# SuperFin_Baseboard_pg8.net
KiCad netlist of a schematic drawn in Altium Designer
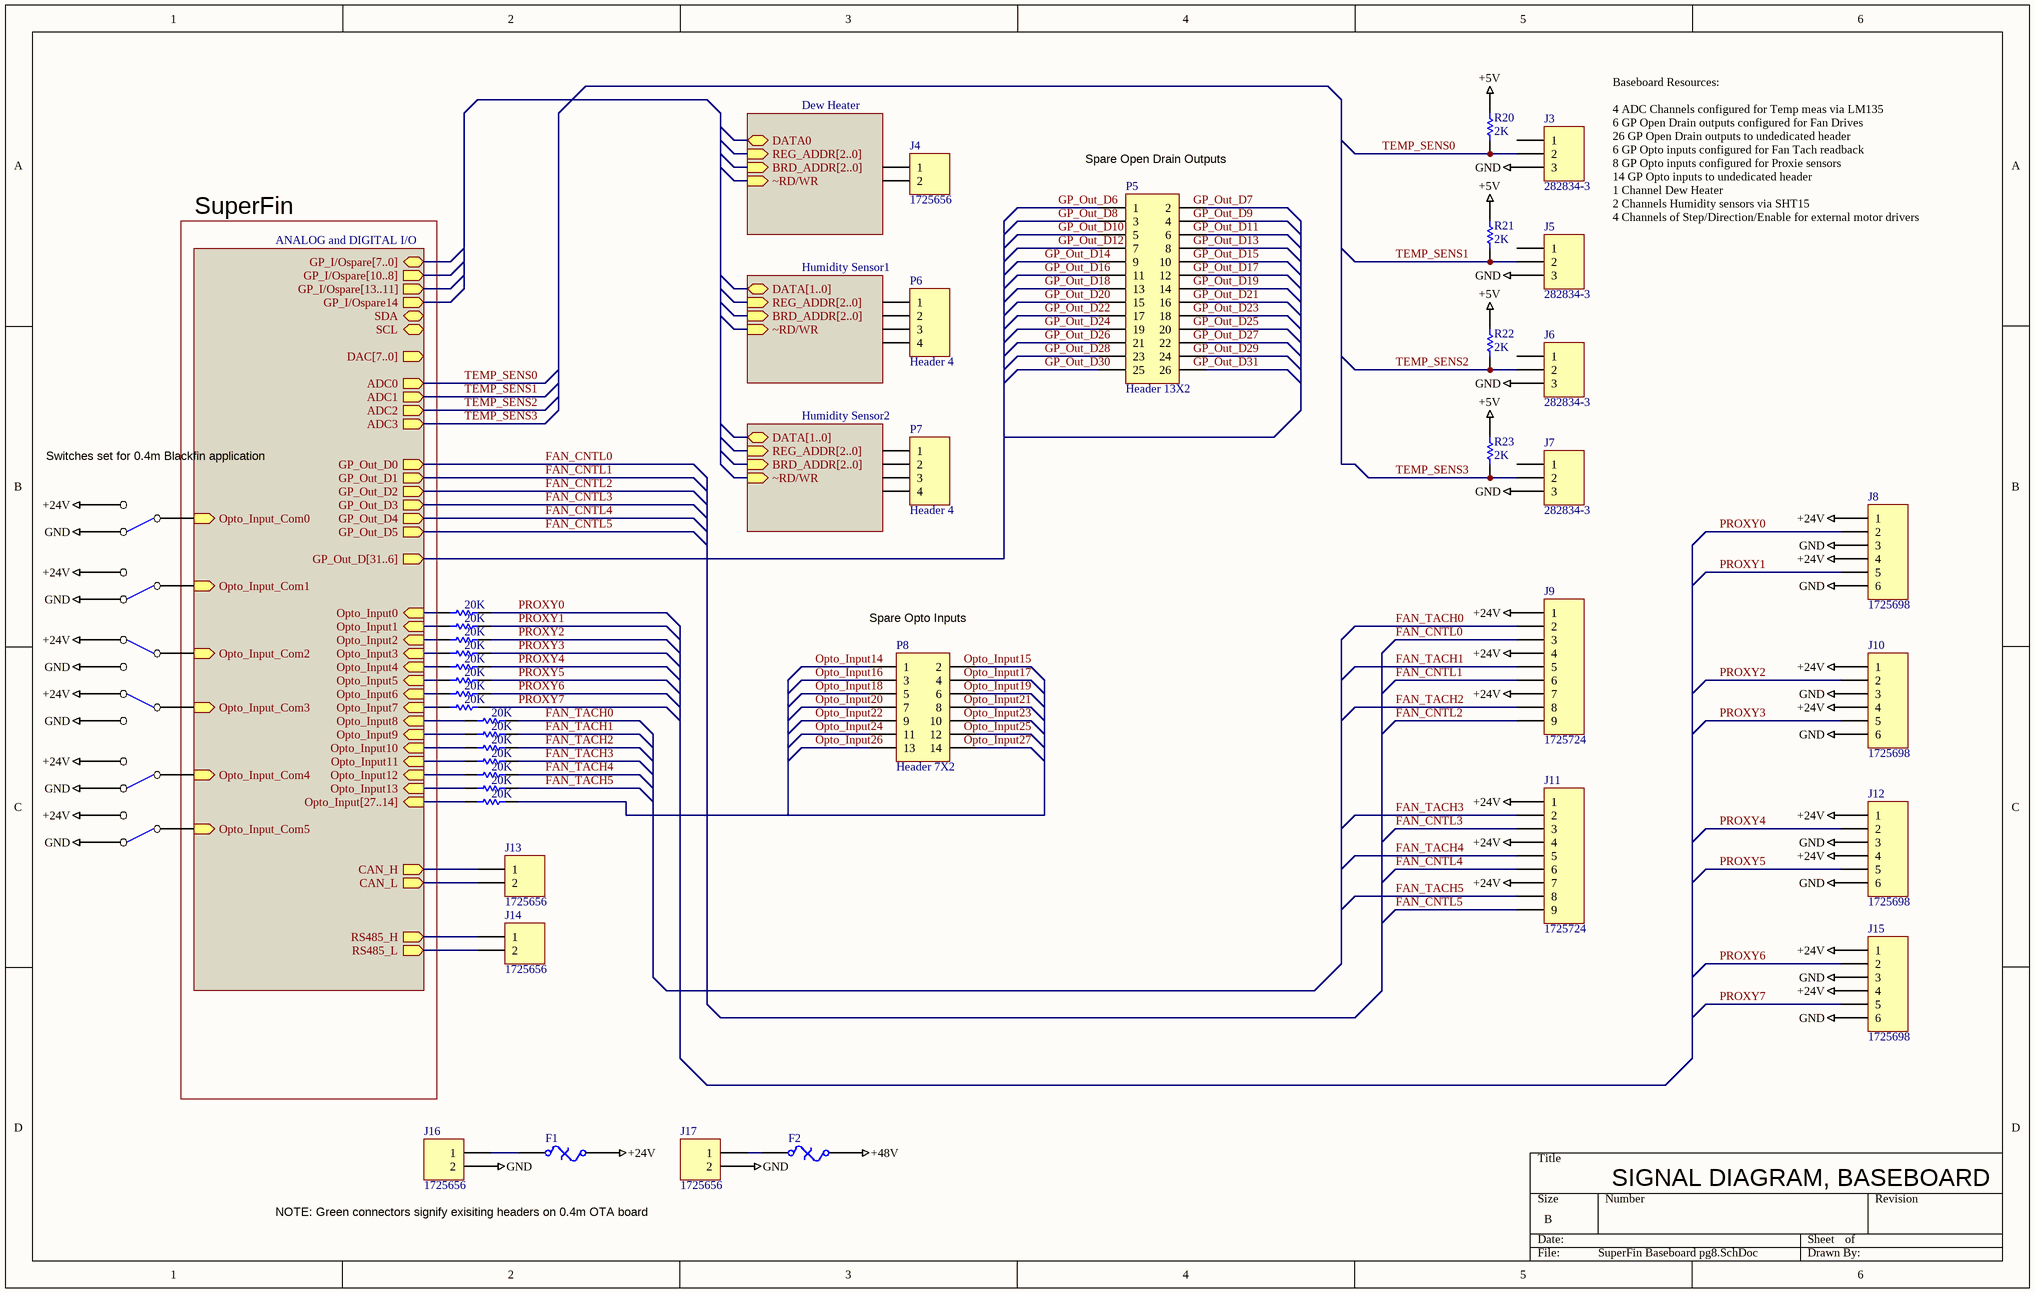
[diagram p0: SuperFin Baseboard pg8.SchDoc]

(export (version "E")
  (design (tool "Eeschema 10.0.6"))
  (components
    (comp (ref "*2") (value "SW_SPDT_DOUG") (libsource (lib "JON_1_Library") (part "SW_SPDT_DOUG")))
    (comp (ref "*3") (value "SW_SPDT_DOUG") (libsource (lib "JON_1_Library") (part "SW_SPDT_DOUG")))
    (comp (ref "*4") (value "SW_SPDT_DOUG") (libsource (lib "JON_1_Library") (part "SW_SPDT_DOUG")))
    (comp (ref "*5") (value "SW_SPDT_DOUG") (libsource (lib "JON_1_Library") (part "SW_SPDT_DOUG")))
    (comp (ref "*6") (value "SW_SPDT_DOUG") (libsource (lib "JON_1_Library") (part "SW_SPDT_DOUG")))
    (comp (ref "*7") (value "SW_SPDT_DOUG") (libsource (lib "JON_1_Library") (part "SW_SPDT_DOUG")))
    (comp (ref "F1")
      (value "Fuse Thermal")
      (footprint "PolySwitch Radial 0.2")
      (description "PolySwitch RUE Series")
      (libsource (lib "Richs Schematic Components") (part "Fuse Thermal"))
    )
    (comp (ref "F2")
      (value "Fuse Thermal")
      (footprint "PolySwitch Radial 0.2")
      (description "PolySwitch RUE Series")
      (libsource (lib "Richs Schematic Components") (part "Fuse Thermal"))
    )
    (comp (ref "J3")
      (value "282834-3")
      (footprint "Tyco Electronics 282834-3")
      (description "Header, 3-Pin")
      (fields (field (name "MANUFACTURER") "Tyco Electronics"))
      (libsource (lib "Miscellaneous Connectors") (part "Header 3"))
    )
    (comp (ref "J4")
      (value "1725656")
      (footprint "Phoenix_1725656")
      (description "Header, 2-Pin")
      (fields (field (name "MANUFACTURER") "Phoenix Contact"))
      (libsource (lib "Miscellaneous Connectors") (part "Header 2"))
    )
    (comp (ref "J5")
      (value "282834-3")
      (footprint "Tyco Electronics 282834-3")
      (description "Header, 3-Pin")
      (fields (field (name "MANUFACTURER") "Tyco Electronics"))
      (libsource (lib "Miscellaneous Connectors") (part "Header 3"))
    )
    (comp (ref "J6")
      (value "282834-3")
      (footprint "Tyco Electronics 282834-3")
      (description "Header, 3-Pin")
      (fields (field (name "MANUFACTURER") "Tyco Electronics"))
      (libsource (lib "Miscellaneous Connectors") (part "Header 3"))
    )
    (comp (ref "J7")
      (value "282834-3")
      (footprint "Tyco Electronics 282834-3")
      (description "Header, 3-Pin")
      (fields (field (name "MANUFACTURER") "Tyco Electronics"))
      (libsource (lib "Miscellaneous Connectors") (part "Header 3"))
    )
    (comp (ref "J8")
      (value "1725698")
      (footprint "1725698")
      (description "Header, 6-Pin")
      (fields (field (name "MANUFACTURER") "Phoenix Contact"))
      (libsource (lib "Miscellaneous Connectors") (part "Header 6"))
    )
    (comp (ref "J9")
      (value "1725724")
      (footprint "1725724")
      (description "Header, 9-Pin")
      (fields (field (name "MANUFACTURER") "Phoenix Contact"))
      (libsource (lib "Miscellaneous Connectors") (part "Header 9"))
    )
    (comp (ref "J10")
      (value "1725698")
      (footprint "1725698")
      (description "Header, 6-Pin")
      (fields (field (name "MANUFACTURER") "Phoenix Contact"))
      (libsource (lib "Miscellaneous Connectors") (part "Header 6"))
    )
    (comp (ref "J11")
      (value "1725724")
      (footprint "1725724")
      (description "Header, 9-Pin")
      (fields (field (name "MANUFACTURER") "Phoenix Contact"))
      (libsource (lib "Miscellaneous Connectors") (part "Header 9"))
    )
    (comp (ref "J12")
      (value "1725698")
      (footprint "1725698")
      (description "Header, 6-Pin")
      (fields (field (name "MANUFACTURER") "Phoenix Contact"))
      (libsource (lib "Miscellaneous Connectors") (part "Header 6"))
    )
    (comp (ref "J13")
      (value "1725656")
      (footprint "Phoenix_1725656")
      (description "Header, 2-Pin")
      (fields (field (name "MANUFACTURER") "Phoenix Contact"))
      (libsource (lib "Miscellaneous Connectors") (part "Header 2"))
    )
    (comp (ref "J14")
      (value "1725656")
      (footprint "Phoenix_1725656")
      (description "Header, 2-Pin")
      (fields (field (name "MANUFACTURER") "Phoenix Contact"))
      (libsource (lib "Miscellaneous Connectors") (part "Header 2"))
    )
    (comp (ref "J15")
      (value "1725698")
      (footprint "1725698")
      (description "Header, 6-Pin")
      (fields (field (name "MANUFACTURER") "Phoenix Contact"))
      (libsource (lib "Miscellaneous Connectors") (part "Header 6"))
    )
    (comp (ref "J16")
      (value "1725656")
      (footprint "Phoenix_1725656")
      (description "Header, 2-Pin")
      (fields (field (name "MANUFACTURER") "Phoenix Contact"))
      (libsource (lib "") (part "Header 2_1"))
    )
    (comp (ref "J17")
      (value "1725656")
      (footprint "Phoenix_1725656")
      (description "Header, 2-Pin")
      (fields (field (name "MANUFACTURER") "Phoenix Contact"))
      (libsource (lib "") (part "Header 2_1"))
    )
    (comp (ref "P5")
      (value "Header 13X2")
      (footprint "HDR2X13")
      (description "Header, 13-Pin, Dual row")
      (fields (field (name "PUBLISHER") "Altium Limited"))
      (libsource (lib "Miscellaneous Connectors") (part "Header 13X2"))
    )
    (comp (ref "P6")
      (value "Header 4")
      (footprint "HDR1X4")
      (description "Header, 4-Pin")
      (fields (field (name "PUBLISHER") "Altium Limited"))
      (libsource (lib "Miscellaneous Connectors") (part "Header 4"))
    )
    (comp (ref "P7")
      (value "Header 4")
      (footprint "HDR1X4")
      (description "Header, 4-Pin")
      (fields (field (name "PUBLISHER") "Altium Limited"))
      (libsource (lib "Miscellaneous Connectors") (part "Header 4"))
    )
    (comp (ref "P8")
      (value "Header 7X2")
      (footprint "HDR2X7")
      (description "Header, 7-Pin, Dual row")
      (fields (field (name "PUBLISHER") "Altium Limited"))
      (libsource (lib "Miscellaneous Connectors") (part "Header 7X2"))
    )
    (comp (ref "R20")
      (value "2K")
      (footprint "AXIAL-0.4")
      (description "Resistor")
      (fields (field (name "Comment") "Res TH"))
      (libsource (lib "Richs Schematic Components") (part "Res TH"))
    )
    (comp (ref "R21")
      (value "2K")
      (footprint "AXIAL-0.4")
      (description "Resistor")
      (fields (field (name "Comment") "Res TH"))
      (libsource (lib "Richs Schematic Components") (part "Res TH"))
    )
    (comp (ref "R22")
      (value "2K")
      (footprint "AXIAL-0.4")
      (description "Resistor")
      (fields (field (name "Comment") "Res TH"))
      (libsource (lib "Richs Schematic Components") (part "Res TH"))
    )
    (comp (ref "R23")
      (value "2K")
      (footprint "AXIAL-0.4")
      (description "Resistor")
      (fields (field (name "Comment") "Res TH"))
      (libsource (lib "Richs Schematic Components") (part "Res TH"))
    )
    (comp (ref "R24")
      (value "20K")
      (footprint "SMD_0805")
      (description "Resistor 0805")
      (fields (field (name "MANUFACTURER") "Vishay/Dale") (field (name "Comment") "Res 0805"))
      (libsource (lib "Richs Schematic Components") (part "Res SMD"))
    )
    (comp (ref "R25")
      (value "20K")
      (footprint "SMD_0805")
      (description "Resistor 0805")
      (fields (field (name "MANUFACTURER") "Vishay/Dale") (field (name "Comment") "Res 0805"))
      (libsource (lib "Richs Schematic Components") (part "Res SMD"))
    )
    (comp (ref "R26")
      (value "20K")
      (footprint "SMD_0805")
      (description "Resistor 0805")
      (fields (field (name "MANUFACTURER") "Vishay/Dale") (field (name "Comment") "Res 0805"))
      (libsource (lib "Richs Schematic Components") (part "Res SMD"))
    )
    (comp (ref "R27")
      (value "20K")
      (footprint "SMD_0805")
      (description "Resistor 0805")
      (fields (field (name "MANUFACTURER") "Vishay/Dale") (field (name "Comment") "Res 0805"))
      (libsource (lib "Richs Schematic Components") (part "Res SMD"))
    )
    (comp (ref "R28")
      (value "20K")
      (footprint "SMD_0805")
      (description "Resistor 0805")
      (fields (field (name "MANUFACTURER") "Vishay/Dale") (field (name "Comment") "Res 0805"))
      (libsource (lib "Richs Schematic Components") (part "Res SMD"))
    )
    (comp (ref "R29")
      (value "20K")
      (footprint "SMD_0805")
      (description "Resistor 0805")
      (fields (field (name "MANUFACTURER") "Vishay/Dale") (field (name "Comment") "Res 0805"))
      (libsource (lib "Richs Schematic Components") (part "Res SMD"))
    )
    (comp (ref "R30")
      (value "20K")
      (footprint "SMD_0805")
      (description "Resistor 0805")
      (fields (field (name "MANUFACTURER") "Vishay/Dale") (field (name "Comment") "Res 0805"))
      (libsource (lib "Richs Schematic Components") (part "Res SMD"))
    )
    (comp (ref "R31")
      (value "20K")
      (footprint "SMD_0805")
      (description "Resistor 0805")
      (fields (field (name "MANUFACTURER") "Vishay/Dale") (field (name "Comment") "Res 0805"))
      (libsource (lib "Richs Schematic Components") (part "Res SMD"))
    )
    (comp (ref "R32")
      (value "20K")
      (footprint "SMD_0805")
      (description "Resistor 0805")
      (fields (field (name "MANUFACTURER") "Vishay/Dale") (field (name "Comment") "Res 0805"))
      (libsource (lib "Richs Schematic Components") (part "Res SMD"))
    )
    (comp (ref "R33")
      (value "20K")
      (footprint "SMD_0805")
      (description "Resistor 0805")
      (fields (field (name "MANUFACTURER") "Vishay/Dale") (field (name "Comment") "Res 0805"))
      (libsource (lib "Richs Schematic Components") (part "Res SMD"))
    )
    (comp (ref "R34")
      (value "20K")
      (footprint "SMD_0805")
      (description "Resistor 0805")
      (fields (field (name "MANUFACTURER") "Vishay/Dale") (field (name "Comment") "Res 0805"))
      (libsource (lib "Richs Schematic Components") (part "Res SMD"))
    )
    (comp (ref "R35")
      (value "20K")
      (footprint "SMD_0805")
      (description "Resistor 0805")
      (fields (field (name "MANUFACTURER") "Vishay/Dale") (field (name "Comment") "Res 0805"))
      (libsource (lib "Richs Schematic Components") (part "Res SMD"))
    )
    (comp (ref "R36")
      (value "20K")
      (footprint "SMD_0805")
      (description "Resistor 0805")
      (fields (field (name "MANUFACTURER") "Vishay/Dale") (field (name "Comment") "Res 0805"))
      (libsource (lib "Richs Schematic Components") (part "Res SMD"))
    )
    (comp (ref "R37")
      (value "20K")
      (footprint "SMD_0805")
      (description "Resistor 0805")
      (fields (field (name "MANUFACTURER") "Vishay/Dale") (field (name "Comment") "Res 0805"))
      (libsource (lib "Richs Schematic Components") (part "Res SMD"))
    )
    (comp (ref "R38")
      (value "20K")
      (footprint "SMD_0805")
      (description "Resistor 0805")
      (fields (field (name "MANUFACTURER") "Vishay/Dale") (field (name "Comment") "Res 0805"))
      (libsource (lib "Richs Schematic Components") (part "Res SMD"))
    )
  )
  (nets
    (net (code "1") (name "+5V") (class "Default")
      (node (ref "R20") (pin "2") (pinfunction "2_2") (pintype "passive"))
      (node (ref "R21") (pin "2") (pinfunction "2_2") (pintype "passive"))
      (node (ref "R22") (pin "2") (pinfunction "2_2") (pintype "passive"))
      (node (ref "R23") (pin "2") (pinfunction "2_2") (pintype "passive"))
    )
    (net (code "2") (name "+24V") (class "Default")
      (node (ref "*2") (pin "NO") (pinfunction "NO_NO") (pintype "passive"))
      (node (ref "*3") (pin "NO") (pinfunction "NO_NO") (pintype "passive"))
      (node (ref "*4") (pin "NC") (pinfunction "NC_NC") (pintype "passive"))
      (node (ref "*5") (pin "NC") (pinfunction "NC_NC") (pintype "passive"))
      (node (ref "*6") (pin "NO") (pinfunction "NO_NO") (pintype "passive"))
      (node (ref "*7") (pin "NO") (pinfunction "NO_NO") (pintype "passive"))
      (node (ref "F1") (pin "2") (pinfunction "2_2") (pintype "passive"))
      (node (ref "J10") (pin "1") (pinfunction "1_1") (pintype "passive"))
      (node (ref "J10") (pin "4") (pinfunction "4_4") (pintype "passive"))
      (node (ref "J11") (pin "1") (pinfunction "1_1") (pintype "passive"))
      (node (ref "J11") (pin "4") (pinfunction "4_4") (pintype "passive"))
      (node (ref "J11") (pin "7") (pinfunction "7_7") (pintype "passive"))
      (node (ref "J12") (pin "1") (pinfunction "1_1") (pintype "passive"))
      (node (ref "J12") (pin "4") (pinfunction "4_4") (pintype "passive"))
      (node (ref "J15") (pin "1") (pinfunction "1_1") (pintype "passive"))
      (node (ref "J15") (pin "4") (pinfunction "4_4") (pintype "passive"))
      (node (ref "J8") (pin "1") (pinfunction "1_1") (pintype "passive"))
      (node (ref "J8") (pin "4") (pinfunction "4_4") (pintype "passive"))
      (node (ref "J9") (pin "1") (pinfunction "1_1") (pintype "passive"))
      (node (ref "J9") (pin "4") (pinfunction "4_4") (pintype "passive"))
      (node (ref "J9") (pin "7") (pinfunction "7_7") (pintype "passive"))
    )
    (net (code "3") (name "+48V") (class "Default")
      (node (ref "F2") (pin "2") (pinfunction "2_2") (pintype "passive"))
    )
    (net (code "7") (name "/CAN_H") (class "Default")
      (node (ref "J13") (pin "1") (pinfunction "1_1") (pintype "passive"))
    )
    (net (code "8") (name "/CAN_L") (class "Default")
      (node (ref "J13") (pin "2") (pinfunction "2_2") (pintype "passive"))
    )
    (net (code "13") (name "/FAN_CNTL0") (class "Default")
      (node (ref "J9") (pin "3") (pinfunction "3_3") (pintype "passive"))
    )
    (net (code "14") (name "/FAN_CNTL1") (class "Default")
      (node (ref "J9") (pin "6") (pinfunction "6_6") (pintype "passive"))
    )
    (net (code "15") (name "/FAN_CNTL2") (class "Default")
      (node (ref "J9") (pin "9") (pinfunction "9_9") (pintype "passive"))
    )
    (net (code "16") (name "/FAN_CNTL3") (class "Default")
      (node (ref "J11") (pin "3") (pinfunction "3_3") (pintype "passive"))
    )
    (net (code "17") (name "/FAN_CNTL4") (class "Default")
      (node (ref "J11") (pin "6") (pinfunction "6_6") (pintype "passive"))
    )
    (net (code "18") (name "/FAN_CNTL5") (class "Default")
      (node (ref "J11") (pin "9") (pinfunction "9_9") (pintype "passive"))
    )
    (net (code "19") (name "/FAN_TACH0") (class "Default")
      (node (ref "J9") (pin "2") (pinfunction "2_2") (pintype "passive"))
      (node (ref "R32") (pin "2") (pinfunction "2_2") (pintype "passive"))
    )
    (net (code "20") (name "/FAN_TACH1") (class "Default")
      (node (ref "J9") (pin "5") (pinfunction "5_5") (pintype "passive"))
      (node (ref "R33") (pin "2") (pinfunction "2_2") (pintype "passive"))
    )
    (net (code "21") (name "/FAN_TACH2") (class "Default")
      (node (ref "J9") (pin "8") (pinfunction "8_8") (pintype "passive"))
      (node (ref "R34") (pin "2") (pinfunction "2_2") (pintype "passive"))
    )
    (net (code "22") (name "/FAN_TACH3") (class "Default")
      (node (ref "J11") (pin "2") (pinfunction "2_2") (pintype "passive"))
      (node (ref "R35") (pin "2") (pinfunction "2_2") (pintype "passive"))
    )
    (net (code "23") (name "/FAN_TACH4") (class "Default")
      (node (ref "J11") (pin "5") (pinfunction "5_5") (pintype "passive"))
      (node (ref "R36") (pin "2") (pinfunction "2_2") (pintype "passive"))
    )
    (net (code "24") (name "/FAN_TACH5") (class "Default")
      (node (ref "J11") (pin "8") (pinfunction "8_8") (pintype "passive"))
      (node (ref "R37") (pin "2") (pinfunction "2_2") (pintype "passive"))
    )
    (net (code "29") (name "/GP_Out_D6") (class "Default")
      (node (ref "P5") (pin "1") (pinfunction "1_1") (pintype "passive"))
    )
    (net (code "31") (name "/GP_Out_D8") (class "Default")
      (node (ref "P5") (pin "3") (pinfunction "3_3") (pintype "passive"))
    )
    (net (code "33") (name "/GP_Out_D10") (class "Default")
      (node (ref "P5") (pin "5") (pinfunction "5_5") (pintype "passive"))
    )
    (net (code "35") (name "/GP_Out_D12") (class "Default")
      (node (ref "P5") (pin "7") (pinfunction "7_7") (pintype "passive"))
    )
    (net (code "37") (name "/GP_Out_D14") (class "Default")
      (node (ref "P5") (pin "9") (pinfunction "9_9") (pintype "passive"))
    )
    (net (code "39") (name "/GP_Out_D16") (class "Default")
      (node (ref "P5") (pin "11") (pinfunction "11_11") (pintype "passive"))
    )
    (net (code "41") (name "/GP_Out_D18") (class "Default")
      (node (ref "P5") (pin "13") (pinfunction "13_13") (pintype "passive"))
    )
    (net (code "43") (name "/GP_Out_D20") (class "Default")
      (node (ref "P5") (pin "15") (pinfunction "15_15") (pintype "passive"))
    )
    (net (code "45") (name "/GP_Out_D22") (class "Default")
      (node (ref "P5") (pin "17") (pinfunction "17_17") (pintype "passive"))
    )
    (net (code "47") (name "/GP_Out_D24") (class "Default")
      (node (ref "P5") (pin "19") (pinfunction "19_19") (pintype "passive"))
    )
    (net (code "49") (name "/GP_Out_D26") (class "Default")
      (node (ref "P5") (pin "21") (pinfunction "21_21") (pintype "passive"))
    )
    (net (code "51") (name "/GP_Out_D28") (class "Default")
      (node (ref "P5") (pin "23") (pinfunction "23_23") (pintype "passive"))
    )
    (net (code "53") (name "/GP_Out_D30") (class "Default")
      (node (ref "P5") (pin "25") (pinfunction "25_25") (pintype "passive"))
    )
    (net (code "56") (name "/Opto_Input0") (class "Default")
      (node (ref "R24") (pin "1") (pinfunction "1_1") (pintype "passive"))
    )
    (net (code "57") (name "/Opto_Input1") (class "Default")
      (node (ref "R25") (pin "1") (pinfunction "1_1") (pintype "passive"))
    )
    (net (code "58") (name "/Opto_Input2") (class "Default")
      (node (ref "R26") (pin "1") (pinfunction "1_1") (pintype "passive"))
    )
    (net (code "59") (name "/Opto_Input3") (class "Default")
      (node (ref "R27") (pin "1") (pinfunction "1_1") (pintype "passive"))
    )
    (net (code "60") (name "/Opto_Input4") (class "Default")
      (node (ref "R28") (pin "1") (pinfunction "1_1") (pintype "passive"))
    )
    (net (code "61") (name "/Opto_Input5") (class "Default")
      (node (ref "R29") (pin "1") (pinfunction "1_1") (pintype "passive"))
    )
    (net (code "62") (name "/Opto_Input6") (class "Default")
      (node (ref "R30") (pin "1") (pinfunction "1_1") (pintype "passive"))
    )
    (net (code "63") (name "/Opto_Input7") (class "Default")
      (node (ref "R31") (pin "1") (pinfunction "1_1") (pintype "passive"))
    )
    (net (code "64") (name "/Opto_Input8") (class "Default")
      (node (ref "R32") (pin "1") (pinfunction "1_1") (pintype "passive"))
    )
    (net (code "65") (name "/Opto_Input9") (class "Default")
      (node (ref "R33") (pin "1") (pinfunction "1_1") (pintype "passive"))
    )
    (net (code "66") (name "/Opto_Input10") (class "Default")
      (node (ref "R34") (pin "1") (pinfunction "1_1") (pintype "passive"))
    )
    (net (code "67") (name "/Opto_Input11") (class "Default")
      (node (ref "R35") (pin "1") (pinfunction "1_1") (pintype "passive"))
    )
    (net (code "68") (name "/Opto_Input12") (class "Default")
      (node (ref "R36") (pin "1") (pinfunction "1_1") (pintype "passive"))
    )
    (net (code "69") (name "/Opto_Input13") (class "Default")
      (node (ref "R37") (pin "1") (pinfunction "1_1") (pintype "passive"))
    )
    (net (code "70") (name "/Opto_Input14") (class "Default")
      (node (ref "P8") (pin "1") (pinfunction "1_1") (pintype "passive"))
    )
    (net (code "72") (name "/Opto_Input16") (class "Default")
      (node (ref "P8") (pin "3") (pinfunction "3_3") (pintype "passive"))
    )
    (net (code "74") (name "/Opto_Input18") (class "Default")
      (node (ref "P8") (pin "5") (pinfunction "5_5") (pintype "passive"))
    )
    (net (code "76") (name "/Opto_Input20") (class "Default")
      (node (ref "P8") (pin "7") (pinfunction "7_7") (pintype "passive"))
    )
    (net (code "78") (name "/Opto_Input22") (class "Default")
      (node (ref "P8") (pin "9") (pinfunction "9_9") (pintype "passive"))
    )
    (net (code "80") (name "/Opto_Input24") (class "Default")
      (node (ref "P8") (pin "11") (pinfunction "11_11") (pintype "passive"))
    )
    (net (code "82") (name "/Opto_Input26") (class "Default")
      (node (ref "P8") (pin "13") (pinfunction "13_13") (pintype "passive"))
    )
    (net (code "84") (name "/Opto_Input[27..14]") (class "Default")
      (node (ref "R38") (pin "1") (pinfunction "1_1") (pintype "passive"))
    )
    (net (code "85") (name "/Opto_Input_Com0") (class "Default")
      (node (ref "*2") (pin "COM") (pinfunction "COM_COM") (pintype "passive"))
    )
    (net (code "86") (name "/Opto_Input_Com1") (class "Default")
      (node (ref "*3") (pin "COM") (pinfunction "COM_COM") (pintype "passive"))
    )
    (net (code "87") (name "/Opto_Input_Com2") (class "Default")
      (node (ref "*4") (pin "COM") (pinfunction "COM_COM") (pintype "passive"))
    )
    (net (code "88") (name "/Opto_Input_Com3") (class "Default")
      (node (ref "*5") (pin "COM") (pinfunction "COM_COM") (pintype "passive"))
    )
    (net (code "89") (name "/Opto_Input_Com4") (class "Default")
      (node (ref "*6") (pin "COM") (pinfunction "COM_COM") (pintype "passive"))
    )
    (net (code "90") (name "/Opto_Input_Com5") (class "Default")
      (node (ref "*7") (pin "COM") (pinfunction "COM_COM") (pintype "passive"))
    )
    (net (code "91") (name "/PROXY0") (class "Default")
      (node (ref "J8") (pin "2") (pinfunction "2_2") (pintype "passive"))
      (node (ref "R24") (pin "2") (pinfunction "2_2") (pintype "passive"))
    )
    (net (code "92") (name "/PROXY1") (class "Default")
      (node (ref "J8") (pin "5") (pinfunction "5_5") (pintype "passive"))
      (node (ref "R25") (pin "2") (pinfunction "2_2") (pintype "passive"))
    )
    (net (code "93") (name "/PROXY2") (class "Default")
      (node (ref "J10") (pin "2") (pinfunction "2_2") (pintype "passive"))
      (node (ref "R26") (pin "2") (pinfunction "2_2") (pintype "passive"))
    )
    (net (code "94") (name "/PROXY3") (class "Default")
      (node (ref "J10") (pin "5") (pinfunction "5_5") (pintype "passive"))
      (node (ref "R27") (pin "2") (pinfunction "2_2") (pintype "passive"))
    )
    (net (code "95") (name "/PROXY4") (class "Default")
      (node (ref "J12") (pin "2") (pinfunction "2_2") (pintype "passive"))
      (node (ref "R28") (pin "2") (pinfunction "2_2") (pintype "passive"))
    )
    (net (code "96") (name "/PROXY5") (class "Default")
      (node (ref "J12") (pin "5") (pinfunction "5_5") (pintype "passive"))
      (node (ref "R29") (pin "2") (pinfunction "2_2") (pintype "passive"))
    )
    (net (code "97") (name "/PROXY6") (class "Default")
      (node (ref "J15") (pin "2") (pinfunction "2_2") (pintype "passive"))
      (node (ref "R30") (pin "2") (pinfunction "2_2") (pintype "passive"))
    )
    (net (code "98") (name "/PROXY7") (class "Default")
      (node (ref "J15") (pin "5") (pinfunction "5_5") (pintype "passive"))
      (node (ref "R31") (pin "2") (pinfunction "2_2") (pintype "passive"))
    )
    (net (code "102") (name "/RS485_H") (class "Default")
      (node (ref "J14") (pin "1") (pinfunction "1_1") (pintype "passive"))
    )
    (net (code "103") (name "/RS485_L") (class "Default")
      (node (ref "J14") (pin "2") (pinfunction "2_2") (pintype "passive"))
    )
    (net (code "106") (name "/TEMP_SENS0") (class "Default")
      (node (ref "J3") (pin "2") (pinfunction "2_2") (pintype "passive"))
      (node (ref "R20") (pin "1") (pinfunction "1_1") (pintype "passive"))
    )
    (net (code "107") (name "/TEMP_SENS1") (class "Default")
      (node (ref "J5") (pin "2") (pinfunction "2_2") (pintype "passive"))
      (node (ref "R21") (pin "1") (pinfunction "1_1") (pintype "passive"))
    )
    (net (code "108") (name "/TEMP_SENS2") (class "Default")
      (node (ref "J6") (pin "2") (pinfunction "2_2") (pintype "passive"))
      (node (ref "R22") (pin "1") (pinfunction "1_1") (pintype "passive"))
    )
    (net (code "109") (name "/TEMP_SENS3") (class "Default")
      (node (ref "J7") (pin "2") (pinfunction "2_2") (pintype "passive"))
      (node (ref "R23") (pin "1") (pinfunction "1_1") (pintype "passive"))
    )
    (net (code "113") (name "GND") (class "Default")
      (node (ref "*2") (pin "NC") (pinfunction "NC_NC") (pintype "passive"))
      (node (ref "*3") (pin "NC") (pinfunction "NC_NC") (pintype "passive"))
      (node (ref "*4") (pin "NO") (pinfunction "NO_NO") (pintype "passive"))
      (node (ref "*5") (pin "NO") (pinfunction "NO_NO") (pintype "passive"))
      (node (ref "*6") (pin "NC") (pinfunction "NC_NC") (pintype "passive"))
      (node (ref "*7") (pin "NC") (pinfunction "NC_NC") (pintype "passive"))
      (node (ref "J10") (pin "3") (pinfunction "3_3") (pintype "passive"))
      (node (ref "J10") (pin "6") (pinfunction "6_6") (pintype "passive"))
      (node (ref "J12") (pin "3") (pinfunction "3_3") (pintype "passive"))
      (node (ref "J12") (pin "6") (pinfunction "6_6") (pintype "passive"))
      (node (ref "J15") (pin "3") (pinfunction "3_3") (pintype "passive"))
      (node (ref "J15") (pin "6") (pinfunction "6_6") (pintype "passive"))
      (node (ref "J16") (pin "2") (pinfunction "2_2") (pintype "passive"))
      (node (ref "J17") (pin "2") (pinfunction "2_2") (pintype "passive"))
      (node (ref "J3") (pin "3") (pinfunction "3_3") (pintype "passive"))
      (node (ref "J5") (pin "3") (pinfunction "3_3") (pintype "passive"))
      (node (ref "J6") (pin "3") (pinfunction "3_3") (pintype "passive"))
      (node (ref "J7") (pin "3") (pinfunction "3_3") (pintype "passive"))
      (node (ref "J8") (pin "3") (pinfunction "3_3") (pintype "passive"))
      (node (ref "J8") (pin "6") (pinfunction "6_6") (pintype "passive"))
    )
    (net (code "114") (name "Net-(F1-Pad1)") (class "Default")
      (node (ref "F1") (pin "1") (pinfunction "1_1") (pintype "passive"))
      (node (ref "J16") (pin "1") (pinfunction "1_1") (pintype "passive"))
    )
    (net (code "115") (name "Net-(F2-Pad1)") (class "Default")
      (node (ref "F2") (pin "1") (pinfunction "1_1") (pintype "passive"))
      (node (ref "J17") (pin "1") (pinfunction "1_1") (pintype "passive"))
    )
    (net (code "116") (name "unconnected-(J3-Pad1)") (class "Default")
      (node (ref "J3") (pin "1") (pinfunction "1_1") (pintype "passive"))
    )
    (net (code "117") (name "unconnected-(J4-Pad1)") (class "Default")
      (node (ref "J4") (pin "1") (pinfunction "1_1") (pintype "passive"))
    )
    (net (code "118") (name "unconnected-(J4-Pad2)") (class "Default")
      (node (ref "J4") (pin "2") (pinfunction "2_2") (pintype "passive"))
    )
    (net (code "119") (name "unconnected-(J5-Pad1)") (class "Default")
      (node (ref "J5") (pin "1") (pinfunction "1_1") (pintype "passive"))
    )
    (net (code "120") (name "unconnected-(J6-Pad1)") (class "Default")
      (node (ref "J6") (pin "1") (pinfunction "1_1") (pintype "passive"))
    )
    (net (code "121") (name "unconnected-(J7-Pad1)") (class "Default")
      (node (ref "J7") (pin "1") (pinfunction "1_1") (pintype "passive"))
    )
    (net (code "122") (name "unconnected-(P5-Pad2)") (class "Default")
      (node (ref "P5") (pin "2") (pinfunction "2_2") (pintype "passive"))
    )
    (net (code "123") (name "unconnected-(P5-Pad4)") (class "Default")
      (node (ref "P5") (pin "4") (pinfunction "4_4") (pintype "passive"))
    )
    (net (code "124") (name "unconnected-(P5-Pad6)") (class "Default")
      (node (ref "P5") (pin "6") (pinfunction "6_6") (pintype "passive"))
    )
    (net (code "125") (name "unconnected-(P5-Pad8)") (class "Default")
      (node (ref "P5") (pin "8") (pinfunction "8_8") (pintype "passive"))
    )
    (net (code "126") (name "unconnected-(P5-Pad10)") (class "Default")
      (node (ref "P5") (pin "10") (pinfunction "10_10") (pintype "passive"))
    )
    (net (code "127") (name "unconnected-(P5-Pad12)") (class "Default")
      (node (ref "P5") (pin "12") (pinfunction "12_12") (pintype "passive"))
    )
    (net (code "128") (name "unconnected-(P5-Pad14)") (class "Default")
      (node (ref "P5") (pin "14") (pinfunction "14_14") (pintype "passive"))
    )
    (net (code "129") (name "unconnected-(P5-Pad16)") (class "Default")
      (node (ref "P5") (pin "16") (pinfunction "16_16") (pintype "passive"))
    )
    (net (code "130") (name "unconnected-(P5-Pad18)") (class "Default")
      (node (ref "P5") (pin "18") (pinfunction "18_18") (pintype "passive"))
    )
    (net (code "131") (name "unconnected-(P5-Pad20)") (class "Default")
      (node (ref "P5") (pin "20") (pinfunction "20_20") (pintype "passive"))
    )
    (net (code "132") (name "unconnected-(P5-Pad22)") (class "Default")
      (node (ref "P5") (pin "22") (pinfunction "22_22") (pintype "passive"))
    )
    (net (code "133") (name "unconnected-(P5-Pad24)") (class "Default")
      (node (ref "P5") (pin "24") (pinfunction "24_24") (pintype "passive"))
    )
    (net (code "134") (name "unconnected-(P5-Pad26)") (class "Default")
      (node (ref "P5") (pin "26") (pinfunction "26_26") (pintype "passive"))
    )
    (net (code "135") (name "unconnected-(P6-Pad1)") (class "Default")
      (node (ref "P6") (pin "1") (pinfunction "1_1") (pintype "passive"))
    )
    (net (code "136") (name "unconnected-(P6-Pad2)") (class "Default")
      (node (ref "P6") (pin "2") (pinfunction "2_2") (pintype "passive"))
    )
    (net (code "137") (name "unconnected-(P6-Pad3)") (class "Default")
      (node (ref "P6") (pin "3") (pinfunction "3_3") (pintype "passive"))
    )
    (net (code "138") (name "unconnected-(P6-Pad4)") (class "Default")
      (node (ref "P6") (pin "4") (pinfunction "4_4") (pintype "passive"))
    )
    (net (code "139") (name "unconnected-(P7-Pad1)") (class "Default")
      (node (ref "P7") (pin "1") (pinfunction "1_1") (pintype "passive"))
    )
    (net (code "140") (name "unconnected-(P7-Pad2)") (class "Default")
      (node (ref "P7") (pin "2") (pinfunction "2_2") (pintype "passive"))
    )
    (net (code "141") (name "unconnected-(P7-Pad3)") (class "Default")
      (node (ref "P7") (pin "3") (pinfunction "3_3") (pintype "passive"))
    )
    (net (code "142") (name "unconnected-(P7-Pad4)") (class "Default")
      (node (ref "P7") (pin "4") (pinfunction "4_4") (pintype "passive"))
    )
    (net (code "143") (name "unconnected-(P8-Pad2)") (class "Default")
      (node (ref "P8") (pin "2") (pinfunction "2_2") (pintype "passive"))
    )
    (net (code "144") (name "unconnected-(P8-Pad4)") (class "Default")
      (node (ref "P8") (pin "4") (pinfunction "4_4") (pintype "passive"))
    )
    (net (code "145") (name "unconnected-(P8-Pad6)") (class "Default")
      (node (ref "P8") (pin "6") (pinfunction "6_6") (pintype "passive"))
    )
    (net (code "146") (name "unconnected-(P8-Pad8)") (class "Default")
      (node (ref "P8") (pin "8") (pinfunction "8_8") (pintype "passive"))
    )
    (net (code "147") (name "unconnected-(P8-Pad10)") (class "Default")
      (node (ref "P8") (pin "10") (pinfunction "10_10") (pintype "passive"))
    )
    (net (code "148") (name "unconnected-(P8-Pad12)") (class "Default")
      (node (ref "P8") (pin "12") (pinfunction "12_12") (pintype "passive"))
    )
    (net (code "149") (name "unconnected-(P8-Pad14)") (class "Default")
      (node (ref "P8") (pin "14") (pinfunction "14_14") (pintype "passive"))
    )
    (net (code "150") (name "unconnected-(R38-Pad2)") (class "Default")
      (node (ref "R38") (pin "2") (pinfunction "2_2") (pintype "passive"))
    )
  )
)
